# 2_LDO.net
KiCad netlist of a schematic drawn in Altium Designer
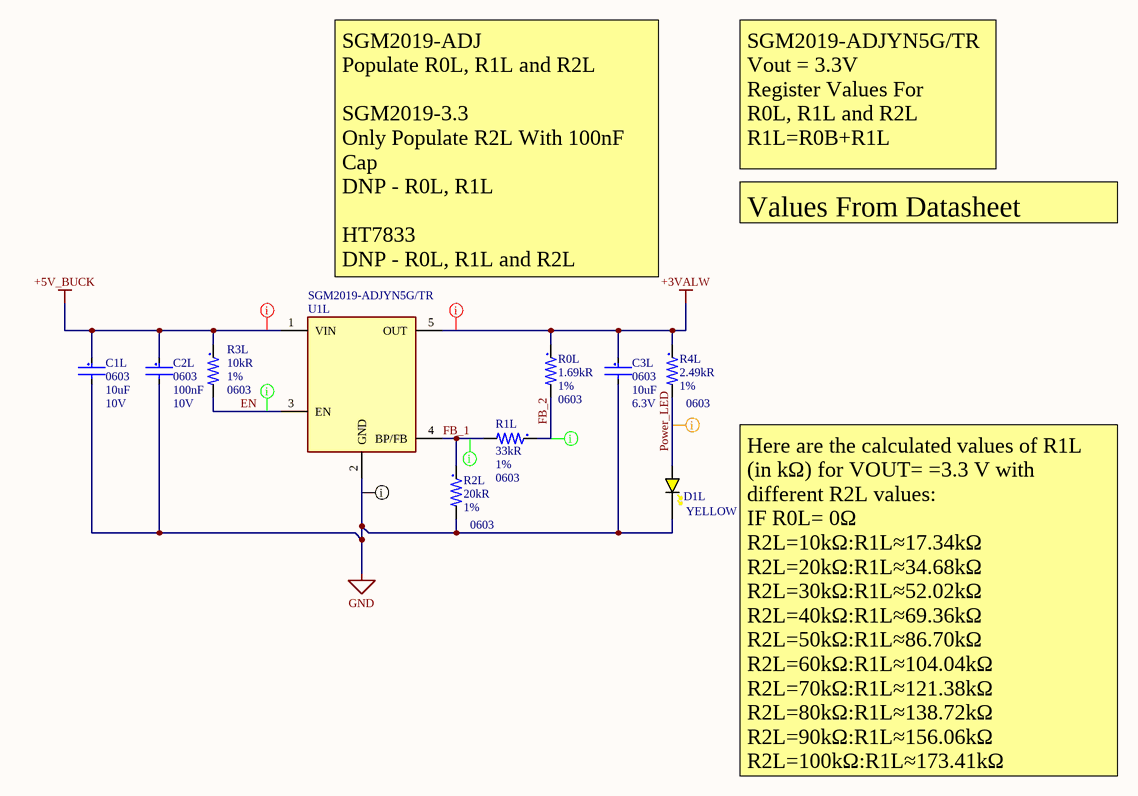
[diagram p0: 2_LDO.SchDoc]

(export (version "E")
  (design (tool "Eeschema 10.0.6"))
  (components
    (comp (ref "C1L")
      (value "10uF")
      (footprint "C0603-IPC_C_No_Silk")
      (description "Multilayer Ceramic Capacitor, 10 uF, 10 V, ± 10%, X5R, 0603 [1608 Metric]")
      (fields
        (field (name "MANUFACTURER") "TDK")
        (field (name "MANUFACTURER PART NUMBER") "C1608X5R1A106K080AC")
        (field (name "CASE/PACKAGE") "0603")
        (field (name "VOLTAGE RATING") "10V")
      )
      (libsource (lib "Lib_Capacitor_0603") (part "10uF_10V"))
    )
    (comp (ref "C2L")
      (value "100nF")
      (footprint "C0603-IPC_C_No_Silk")
      (description "Multilayer Ceramic Capacitor, 0.1 uF, 10 V, ± 10%, X7R, 0603 [1608 Metric]")
      (fields
        (field (name "MANUFACTURER") "KEMET")
        (field (name "MANUFACTURER PART NUMBER") "C0603C104K8RACTU")
        (field (name "CASE/PACKAGE") "0603")
        (field (name "VOLTAGE RATING") "10V")
      )
      (libsource (lib "Lib_Capacitor_0603") (part "100nF_10V"))
    )
    (comp (ref "C3L")
      (value "10uF")
      (footprint "C0603-IPC_C_No_Silk")
      (description "Multilayer Ceramic Capacitor, 10 uF, 6.3 V, ± 10%, X5R, 0603 [1608 Metric]")
      (fields
        (field (name "MANUFACTURER") "Samsung")
        (field (name "MANUFACTURER PART NUMBER") "CL10A106KQ8NNNC")
        (field (name "CASE/PACKAGE") "0603")
        (field (name "VOLTAGE RATING") "6.3V")
      )
      (libsource (lib "Lib_Capacitor_0603") (part "10uF_6.3V"))
    )
    (comp (ref "D1L")
      (value "YELLOW")
      (footprint "LED_0603_YELLOW")
      (description "LED 0603 YELLOW SMD")
      (libsource (lib "Lib_LED") (part "LED_0603_YELLOW"))
    )
    (comp (ref "R0L")
      (value "1.69kR")
      (footprint "R0603-MFG")
      (description "Surface Mount Thick Film Chip Resistor 0603 Case 1.69K Ohms 1% Tolerance 100 PPM")
      (fields
        (field (name "MANUFACTURER") "Rohm")
        (field (name "MANUFACTURER PART NUMBER") "MCR03EZPFX1691")
        (field (name "TOLERANCE") "1%")
        (field (name "CASE/PACKAGE") "0603")
      )
      (libsource (lib "Lib_Register_0603") (part "1.69K"))
    )
    (comp (ref "R1L")
      (value "33kR")
      (footprint "R0603-MFG")
      (description "Res Thick Film 0603 33K Ohm 1% 0.1W(1/10W) ±100ppm/C Pad SMD Automotive T/R")
      (fields
        (field (name "MANUFACTURER") "Panasonic")
        (field (name "MANUFACTURER PART NUMBER") "ERJ-3EKF3302V")
        (field (name "TOLERANCE") "1%")
        (field (name "CASE/PACKAGE") "0603")
      )
      (libsource (lib "Lib_Register_0603") (part "33K"))
    )
    (comp (ref "R2L")
      (value "20kR")
      (footprint "R0603-MFG")
      (description "SMD Chip Resistor, 20 kOhm, ± 1%, 100 mW, 0603 [1608 Metric], Thick Film, General Purpose")
      (fields
        (field (name "MANUFACTURER") "Bourns")
        (field (name "MANUFACTURER PART NUMBER") "CR0603-FX-2002ELF")
        (field (name "TOLERANCE") "1%")
        (field (name "CASE/PACKAGE") "0603")
      )
      (libsource (lib "Lib_Register_0603") (part "20K"))
    )
    (comp (ref "R3L")
      (value "10kR")
      (footprint "R0603-MFG")
      (description "SMD Chip Resistor, 10 kOhm, ± 1%, 100 mW, 0603 [1608 Metric], Thick Film, General Purpose")
      (fields
        (field (name "MANUFACTURER") "Yageo")
        (field (name "MANUFACTURER PART NUMBER") "RC0603FR-0710KL")
        (field (name "TOLERANCE") "1%")
        (field (name "CASE/PACKAGE") "0603")
      )
      (libsource (lib "Lib_Register_0603") (part "10K"))
    )
    (comp (ref "R4L")
      (value "2.49kR")
      (footprint "R0603-MFG")
      (description "Res Thick Film 0603 2.49K Ohm 1% 1/10W ±100ppm/°C Molded SMD SMD Paper T/R")
      (fields
        (field (name "MANUFACTURER") "Rohm")
        (field (name "MANUFACTURER PART NUMBER") "MCR03EZPFX2491")
        (field (name "TOLERANCE") "1%")
        (field (name "CASE/PACKAGE") "0603")
      )
      (libsource (lib "Lib_Register_0603") (part "2.49K"))
    )
    (comp (ref "U1L")
      (value "SGM2019-ADJYN5G/TR")
      (footprint "TSOT-23-5-IPC-A")
      (description "LDO U-Reg Adj 0, 3A SOT23-5")
      (fields (field (name "MANUFACTURER") "SG Micro"))
      (libsource (lib "Lib_LDO") (part "SGM2019-ADJYN5G/TR"))
    )
  )
  (nets
    (net (code "1") (name "+3VALW") (class "Default")
      (node (ref "C3L") (pin "1") (pinfunction "1_1") (pintype "passive"))
      (node (ref "R0L") (pin "1") (pinfunction "1_1") (pintype "passive"))
      (node (ref "R4L") (pin "1") (pinfunction "1_1") (pintype "passive"))
      (node (ref "U1L") (pin "5") (pinfunction "OUT_5") (pintype "power_in"))
    )
    (net (code "2") (name "+5V_BUCK") (class "Default")
      (node (ref "C1L") (pin "1") (pinfunction "1_1") (pintype "passive"))
      (node (ref "C2L") (pin "1") (pinfunction "1_1") (pintype "passive"))
      (node (ref "R3L") (pin "1") (pinfunction "1_1") (pintype "passive"))
      (node (ref "U1L") (pin "1") (pinfunction "VIN_1") (pintype "power_in"))
    )
    (net (code "3") (name "/EN") (class "Default")
      (node (ref "R3L") (pin "2") (pinfunction "2_2") (pintype "passive"))
      (node (ref "U1L") (pin "3") (pinfunction "EN_3") (pintype "passive"))
    )
    (net (code "4") (name "/FB_1") (class "Default")
      (node (ref "R1L") (pin "2") (pinfunction "2_2") (pintype "passive"))
      (node (ref "R2L") (pin "1") (pinfunction "1_1") (pintype "passive"))
      (node (ref "U1L") (pin "4") (pinfunction "BP/FB_4") (pintype "passive"))
    )
    (net (code "5") (name "/FB_2") (class "Default")
      (node (ref "R0L") (pin "2") (pinfunction "2_2") (pintype "passive"))
      (node (ref "R1L") (pin "1") (pinfunction "1_1") (pintype "passive"))
    )
    (net (code "6") (name "/Power_LED") (class "Default")
      (node (ref "D1L") (pin "2") (pinfunction "A_2") (pintype "passive"))
      (node (ref "R4L") (pin "2") (pinfunction "2_2") (pintype "passive"))
    )
    (net (code "7") (name "GND") (class "Default")
      (node (ref "C1L") (pin "2") (pinfunction "2_2") (pintype "passive"))
      (node (ref "C2L") (pin "2") (pinfunction "2_2") (pintype "passive"))
      (node (ref "C3L") (pin "2") (pinfunction "2_2") (pintype "passive"))
      (node (ref "D1L") (pin "1") (pinfunction "K_1") (pintype "passive"))
      (node (ref "R2L") (pin "2") (pinfunction "2_2") (pintype "passive"))
      (node (ref "U1L") (pin "2") (pinfunction "GND_2") (pintype "power_in"))
    )
  )
)
